# PEM-Adapter_1_0_0.net
KiCad netlist of a schematic drawn in EAGLE
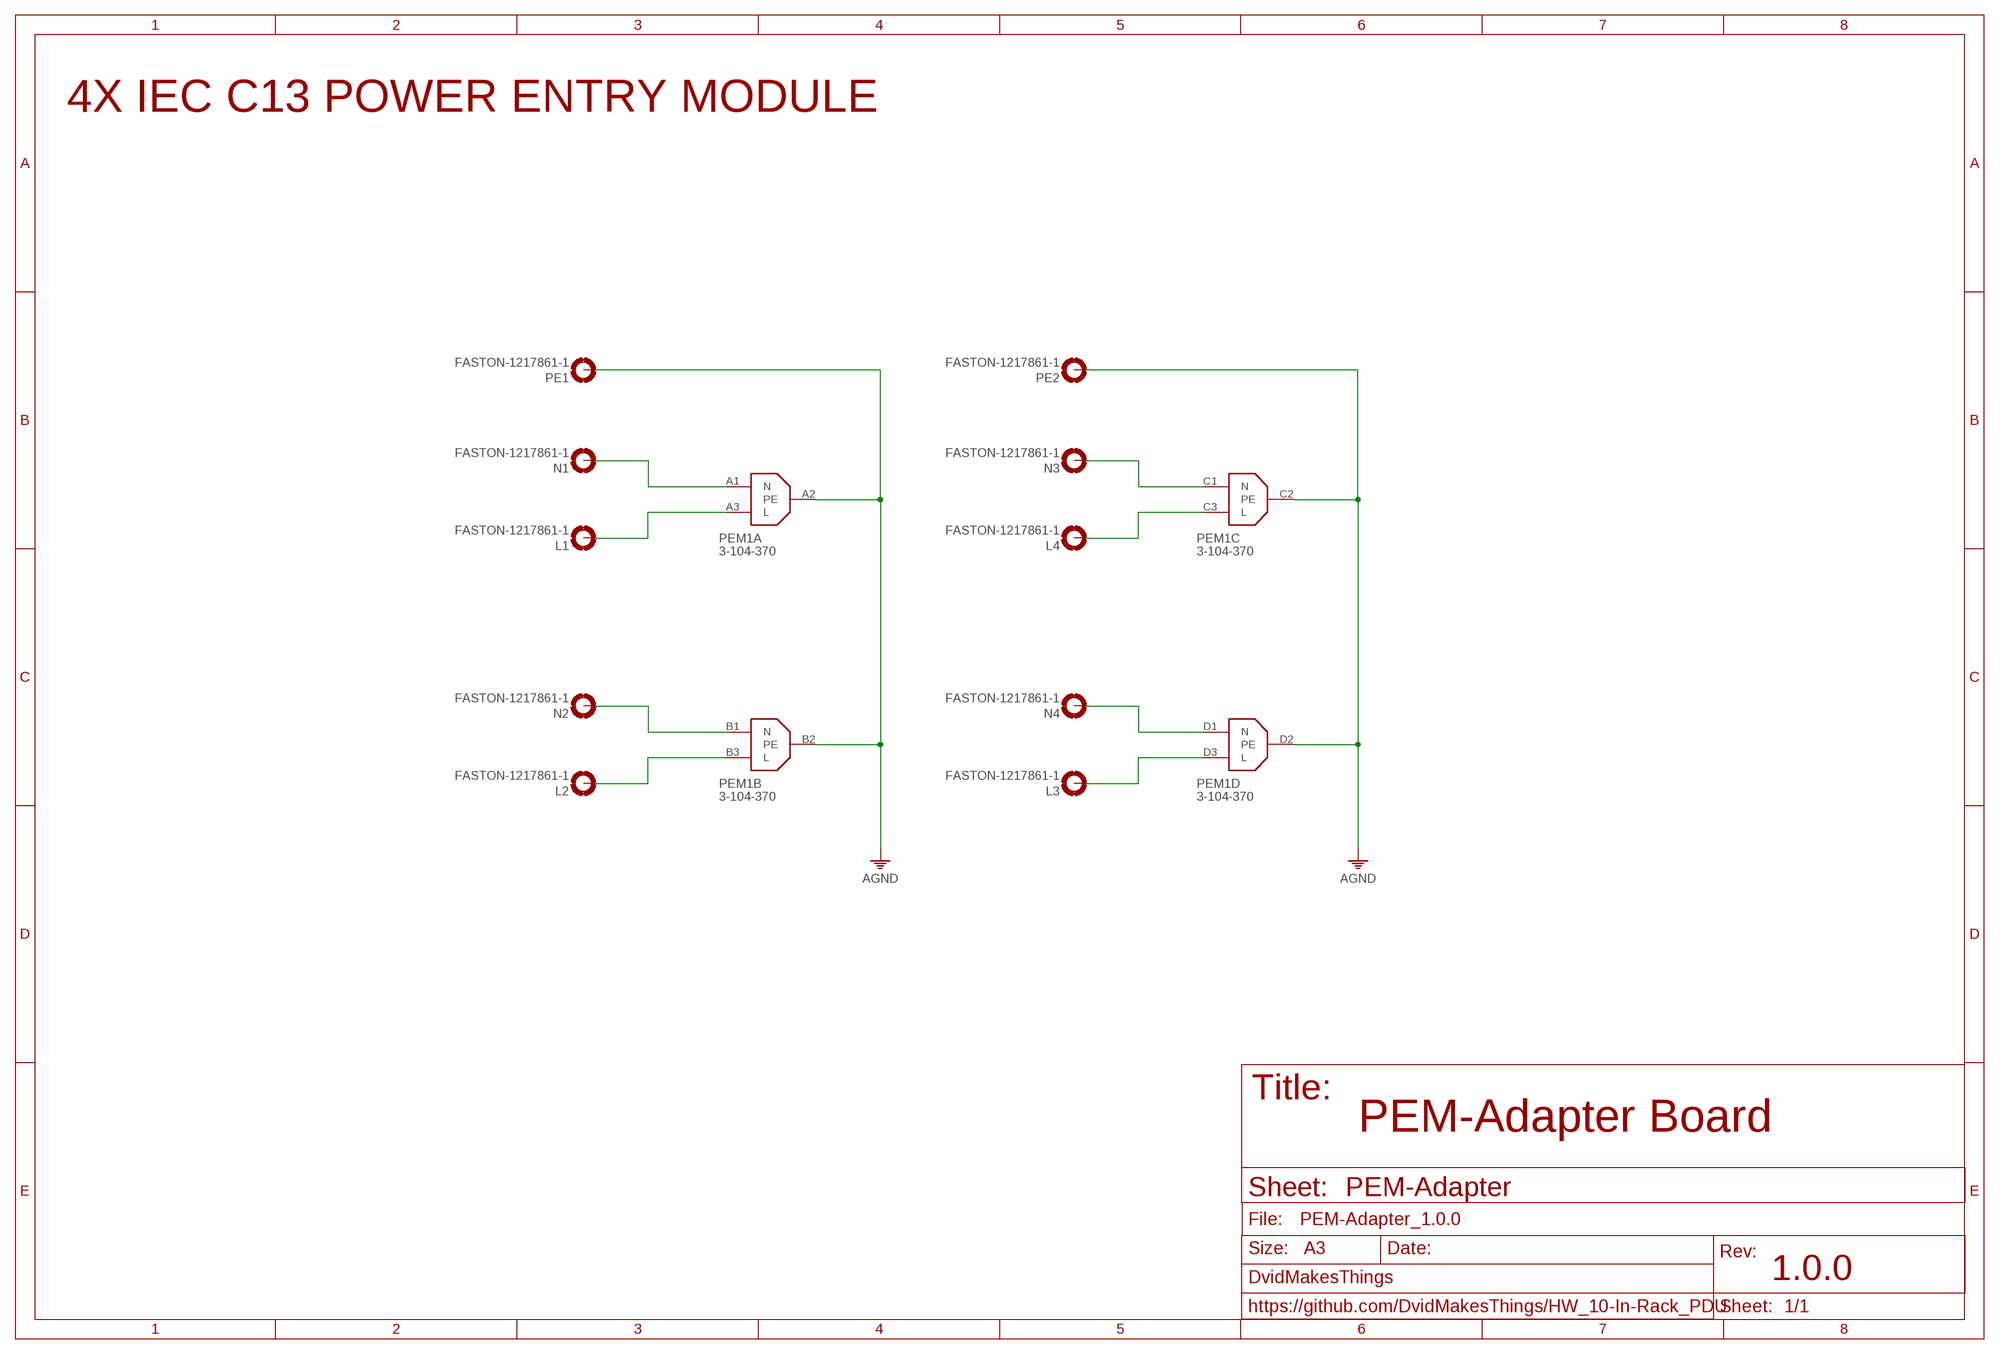
[diagram p0: schematic, sheet 1]

(export (version "E")
  (design (tool "Eeschema 10.0.6"))
  (components
    (comp (ref "L1")
      (value "FASTON-1217861-1")
      (footprint "eagle-import:1217861-1")
      (fields
        (field (name "LCSC_PART") "C428480")
        (field (name "MANUFACTURER") "TE CONNECTIVITY")
        (field (name "MPN") "1217861-1")
      )
      (libsource (lib "eagle-import") (part "FASTON-1217861-1"))
    )
    (comp (ref "L2")
      (value "FASTON-1217861-1")
      (footprint "eagle-import:1217861-1")
      (fields
        (field (name "LCSC_PART") "C428480")
        (field (name "MANUFACTURER") "TE CONNECTIVITY")
        (field (name "MPN") "1217861-1")
      )
      (libsource (lib "eagle-import") (part "FASTON-1217861-1"))
    )
    (comp (ref "L3")
      (value "FASTON-1217861-1")
      (footprint "eagle-import:1217861-1")
      (fields
        (field (name "LCSC_PART") "C428480")
        (field (name "MANUFACTURER") "TE CONNECTIVITY")
        (field (name "MPN") "1217861-1")
      )
      (libsource (lib "eagle-import") (part "FASTON-1217861-1"))
    )
    (comp (ref "L4")
      (value "FASTON-1217861-1")
      (footprint "eagle-import:1217861-1")
      (fields
        (field (name "LCSC_PART") "C428480")
        (field (name "MANUFACTURER") "TE CONNECTIVITY")
        (field (name "MPN") "1217861-1")
      )
      (libsource (lib "eagle-import") (part "FASTON-1217861-1"))
    )
    (comp (ref "N1")
      (value "FASTON-1217861-1")
      (footprint "eagle-import:1217861-1")
      (fields
        (field (name "LCSC_PART") "C428480")
        (field (name "MANUFACTURER") "TE CONNECTIVITY")
        (field (name "MPN") "1217861-1")
      )
      (libsource (lib "eagle-import") (part "FASTON-1217861-1"))
    )
    (comp (ref "N2")
      (value "FASTON-1217861-1")
      (footprint "eagle-import:1217861-1")
      (fields
        (field (name "LCSC_PART") "C428480")
        (field (name "MANUFACTURER") "TE CONNECTIVITY")
        (field (name "MPN") "1217861-1")
      )
      (libsource (lib "eagle-import") (part "FASTON-1217861-1"))
    )
    (comp (ref "N3")
      (value "FASTON-1217861-1")
      (footprint "eagle-import:1217861-1")
      (fields
        (field (name "LCSC_PART") "C428480")
        (field (name "MANUFACTURER") "TE CONNECTIVITY")
        (field (name "MPN") "1217861-1")
      )
      (libsource (lib "eagle-import") (part "FASTON-1217861-1"))
    )
    (comp (ref "N4")
      (value "FASTON-1217861-1")
      (footprint "eagle-import:1217861-1")
      (fields
        (field (name "LCSC_PART") "C428480")
        (field (name "MANUFACTURER") "TE CONNECTIVITY")
        (field (name "MPN") "1217861-1")
      )
      (libsource (lib "eagle-import") (part "FASTON-1217861-1"))
    )
    (comp (ref "PE1")
      (value "FASTON-1217861-1")
      (footprint "eagle-import:1217861-1")
      (fields
        (field (name "LCSC_PART") "C428480")
        (field (name "MANUFACTURER") "TE CONNECTIVITY")
        (field (name "MPN") "1217861-1")
      )
      (libsource (lib "eagle-import") (part "FASTON-1217861-1"))
    )
    (comp (ref "PE2")
      (value "FASTON-1217861-1")
      (footprint "eagle-import:1217861-1")
      (fields
        (field (name "LCSC_PART") "C428480")
        (field (name "MANUFACTURER") "TE CONNECTIVITY")
        (field (name "MPN") "1217861-1")
      )
      (libsource (lib "eagle-import") (part "FASTON-1217861-1"))
    )
    (comp (ref "PEM1")
      (value "3-104-370")
      (footprint "eagle-import:3-104-370")
      (fields (field (name "MANUFACTURER") "SCHURTER Inc."))
      (libsource (lib "eagle-import") (part "3-104-370"))
    )
  )
  (nets
    (net (code "1") (name "AGND") (class "Default")
      (node (ref "PE1") (pin "1") (pinfunction "MOUNT_1") (pintype "passive"))
      (node (ref "PE1") (pin "2") (pinfunction "MOUNT_2") (pintype "passive"))
      (node (ref "PE2") (pin "1") (pinfunction "MOUNT_1") (pintype "passive"))
      (node (ref "PE2") (pin "2") (pinfunction "MOUNT_2") (pintype "passive"))
      (node (ref "PEM1") (pin "A2") (pinfunction "PE_A2") (pintype "bidirectional"))
      (node (ref "PEM1") (pin "B2") (pinfunction "PE_B2") (pintype "bidirectional"))
      (node (ref "PEM1") (pin "C2") (pinfunction "PE_C2") (pintype "bidirectional"))
      (node (ref "PEM1") (pin "D2") (pinfunction "PE_D2") (pintype "bidirectional"))
    )
    (net (code "2") (name "Net-(PEM1A-L)") (class "Default")
      (node (ref "L1") (pin "1") (pinfunction "MOUNT_1") (pintype "passive"))
      (node (ref "L1") (pin "2") (pinfunction "MOUNT_2") (pintype "passive"))
      (node (ref "PEM1") (pin "A3") (pinfunction "L_A3") (pintype "bidirectional"))
    )
    (net (code "3") (name "Net-(PEM1A-N)") (class "Default")
      (node (ref "N1") (pin "1") (pinfunction "MOUNT_1") (pintype "passive"))
      (node (ref "N1") (pin "2") (pinfunction "MOUNT_2") (pintype "passive"))
      (node (ref "PEM1") (pin "A1") (pinfunction "N_A1") (pintype "bidirectional"))
    )
    (net (code "4") (name "Net-(PEM1B-L)") (class "Default")
      (node (ref "L2") (pin "1") (pinfunction "MOUNT_1") (pintype "passive"))
      (node (ref "L2") (pin "2") (pinfunction "MOUNT_2") (pintype "passive"))
      (node (ref "PEM1") (pin "B3") (pinfunction "L_B3") (pintype "bidirectional"))
    )
    (net (code "5") (name "Net-(PEM1B-N)") (class "Default")
      (node (ref "N2") (pin "1") (pinfunction "MOUNT_1") (pintype "passive"))
      (node (ref "N2") (pin "2") (pinfunction "MOUNT_2") (pintype "passive"))
      (node (ref "PEM1") (pin "B1") (pinfunction "N_B1") (pintype "bidirectional"))
    )
    (net (code "6") (name "Net-(PEM1C-L)") (class "Default")
      (node (ref "L4") (pin "1") (pinfunction "MOUNT_1") (pintype "passive"))
      (node (ref "L4") (pin "2") (pinfunction "MOUNT_2") (pintype "passive"))
      (node (ref "PEM1") (pin "C3") (pinfunction "L_C3") (pintype "bidirectional"))
    )
    (net (code "7") (name "Net-(PEM1C-N)") (class "Default")
      (node (ref "N3") (pin "1") (pinfunction "MOUNT_1") (pintype "passive"))
      (node (ref "N3") (pin "2") (pinfunction "MOUNT_2") (pintype "passive"))
      (node (ref "PEM1") (pin "C1") (pinfunction "N_C1") (pintype "bidirectional"))
    )
    (net (code "8") (name "Net-(PEM1D-L)") (class "Default")
      (node (ref "L3") (pin "1") (pinfunction "MOUNT_1") (pintype "passive"))
      (node (ref "L3") (pin "2") (pinfunction "MOUNT_2") (pintype "passive"))
      (node (ref "PEM1") (pin "D3") (pinfunction "L_D3") (pintype "bidirectional"))
    )
    (net (code "9") (name "Net-(PEM1D-N)") (class "Default")
      (node (ref "N4") (pin "1") (pinfunction "MOUNT_1") (pintype "passive"))
      (node (ref "N4") (pin "2") (pinfunction "MOUNT_2") (pintype "passive"))
      (node (ref "PEM1") (pin "D1") (pinfunction "N_D1") (pintype "bidirectional"))
    )
  )
)
